# AutoPilotPanel_-_Part_1.net
KiCad netlist of a schematic drawn in EAGLE
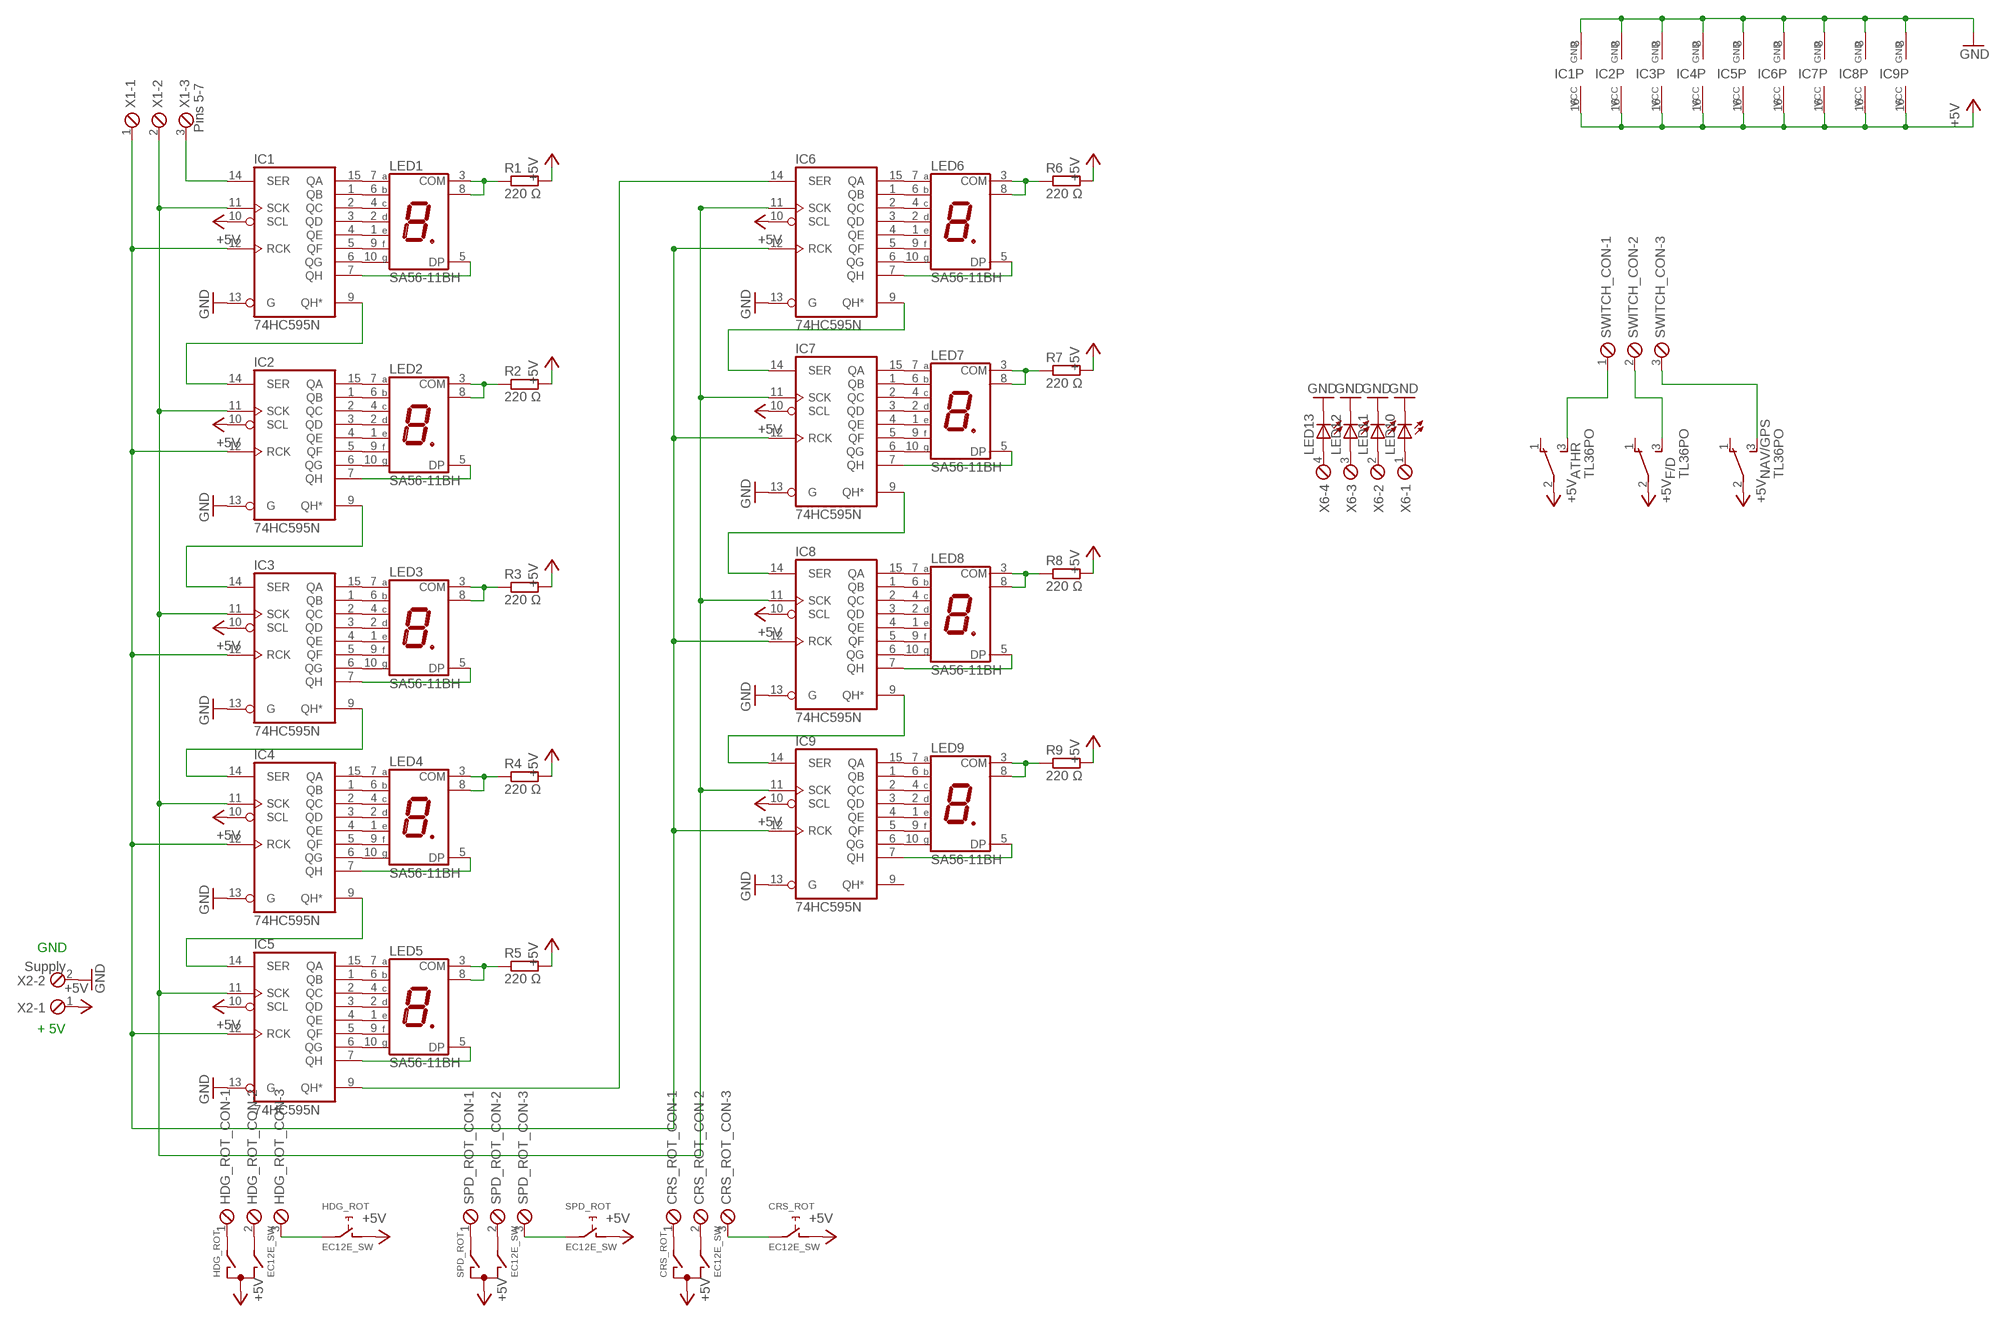
[diagram p0: schematic, sheet 1]

(export (version "E")
  (design (tool "Eeschema 10.0.6"))
  (components
    (comp (ref "ATHR")
      (value "TL36PO")
      (footprint "eagle-import:TL3XPO")
      (libsource (lib "eagle-import") (part "TL36PO"))
    )
    (comp (ref "CRS_ROT")
      (value "EC12E_SW")
      (footprint "eagle-import:ALPS_EC12E_SW")
      (fields (field (name "MPN") "EC12E2424407"))
      (libsource (lib "eagle-import") (part "EC12E_SW"))
    )
    (comp (ref "CRS_ROT_CON")
      (value "MPT3")
      (footprint "eagle-import:3POL254")
      (libsource (lib "eagle-import") (part "MPT3"))
    )
    (comp (ref "F/D")
      (value "TL36PO")
      (footprint "eagle-import:TL3XPO")
      (libsource (lib "eagle-import") (part "TL36PO"))
    )
    (comp (ref "HDG_ROT")
      (value "EC12E_SW")
      (footprint "eagle-import:ALPS_EC12E_SW")
      (fields (field (name "MPN") "EC12E2424407"))
      (libsource (lib "eagle-import") (part "EC12E_SW"))
    )
    (comp (ref "HDG_ROT_CON")
      (value "MPT3")
      (footprint "eagle-import:3POL254")
      (libsource (lib "eagle-import") (part "MPT3"))
    )
    (comp (ref "IC1")
      (value "74HC595N")
      (footprint "eagle-import:DIL16")
      (libsource (lib "eagle-import") (part "74595NHC"))
    )
    (comp (ref "IC2")
      (value "74HC595N")
      (footprint "eagle-import:DIL16")
      (libsource (lib "eagle-import") (part "74595NHC"))
    )
    (comp (ref "IC3")
      (value "74HC595N")
      (footprint "eagle-import:DIL16")
      (libsource (lib "eagle-import") (part "74595NHC"))
    )
    (comp (ref "IC4")
      (value "74HC595N")
      (footprint "eagle-import:DIL16")
      (libsource (lib "eagle-import") (part "74595NHC"))
    )
    (comp (ref "IC5")
      (value "74HC595N")
      (footprint "eagle-import:DIL16")
      (libsource (lib "eagle-import") (part "74595NHC"))
    )
    (comp (ref "IC6")
      (value "74HC595N")
      (footprint "eagle-import:DIL16")
      (libsource (lib "eagle-import") (part "74595NHC"))
    )
    (comp (ref "IC7")
      (value "74HC595N")
      (footprint "eagle-import:DIL16")
      (libsource (lib "eagle-import") (part "74595NHC"))
    )
    (comp (ref "IC8")
      (value "74HC595N")
      (footprint "eagle-import:DIL16")
      (libsource (lib "eagle-import") (part "74595NHC"))
    )
    (comp (ref "IC9")
      (value "74HC595N")
      (footprint "eagle-import:DIL16")
      (libsource (lib "eagle-import") (part "74595NHC"))
    )
    (comp (ref "LED1")
      (value "SA56-11BH")
      (footprint "eagle-import:SA56-11")
      (libsource (lib "eagle-import") (part "7-SEG_SA56-11"))
    )
    (comp (ref "LED2")
      (value "SA56-11BH")
      (footprint "eagle-import:SA56-11")
      (libsource (lib "eagle-import") (part "7-SEG_SA56-11"))
    )
    (comp (ref "LED3")
      (value "SA56-11BH")
      (footprint "eagle-import:SA56-11")
      (libsource (lib "eagle-import") (part "7-SEG_SA56-11"))
    )
    (comp (ref "LED4")
      (value "SA56-11BH")
      (footprint "eagle-import:SA56-11")
      (libsource (lib "eagle-import") (part "7-SEG_SA56-11"))
    )
    (comp (ref "LED5")
      (value "SA56-11BH")
      (footprint "eagle-import:SA56-11")
      (libsource (lib "eagle-import") (part "7-SEG_SA56-11"))
    )
    (comp (ref "LED6")
      (value "SA56-11BH")
      (footprint "eagle-import:SA56-11")
      (libsource (lib "eagle-import") (part "7-SEG_SA56-11"))
    )
    (comp (ref "LED7")
      (value "SA56-11BH")
      (footprint "eagle-import:SA56-11")
      (libsource (lib "eagle-import") (part "7-SEG_SA56-11"))
    )
    (comp (ref "LED8")
      (value "SA56-11BH")
      (footprint "eagle-import:SA56-11")
      (libsource (lib "eagle-import") (part "7-SEG_SA56-11"))
    )
    (comp (ref "LED9")
      (value "SA56-11BH")
      (footprint "eagle-import:SA56-11")
      (libsource (lib "eagle-import") (part "7-SEG_SA56-11"))
    )
    (comp (ref "LED10")
      (value "LED5MM")
      (footprint "eagle-import:LED5MM")
      (libsource (lib "eagle-import") (part "LED5MM"))
    )
    (comp (ref "LED11")
      (value "LED5MM")
      (footprint "eagle-import:LED5MM")
      (libsource (lib "eagle-import") (part "LED5MM"))
    )
    (comp (ref "LED12")
      (value "LED5MM")
      (footprint "eagle-import:LED5MM")
      (libsource (lib "eagle-import") (part "LED5MM"))
    )
    (comp (ref "LED13")
      (value "LED5MM")
      (footprint "eagle-import:LED5MM")
      (libsource (lib "eagle-import") (part "LED5MM"))
    )
    (comp (ref "NAV/GPS")
      (value "TL36PO")
      (footprint "eagle-import:TL3XPO")
      (libsource (lib "eagle-import") (part "TL36PO"))
    )
    (comp (ref "R1")
      (value "220 Ω")
      (footprint "eagle-import:0207_12")
      (libsource (lib "eagle-import") (part "R-EU_0207/12"))
    )
    (comp (ref "R2")
      (value "220 Ω")
      (footprint "eagle-import:0207_12")
      (libsource (lib "eagle-import") (part "R-EU_0207/12"))
    )
    (comp (ref "R3")
      (value "220 Ω")
      (footprint "eagle-import:0207_12")
      (libsource (lib "eagle-import") (part "R-EU_0207/12"))
    )
    (comp (ref "R4")
      (value "220 Ω")
      (footprint "eagle-import:0207_12")
      (libsource (lib "eagle-import") (part "R-EU_0207/12"))
    )
    (comp (ref "R5")
      (value "220 Ω")
      (footprint "eagle-import:0207_12")
      (libsource (lib "eagle-import") (part "R-EU_0207/12"))
    )
    (comp (ref "R6")
      (value "220 Ω")
      (footprint "eagle-import:0207_12")
      (libsource (lib "eagle-import") (part "R-EU_0207/12"))
    )
    (comp (ref "R7")
      (value "220 Ω")
      (footprint "eagle-import:0207_12")
      (libsource (lib "eagle-import") (part "R-EU_0207/12"))
    )
    (comp (ref "R8")
      (value "220 Ω")
      (footprint "eagle-import:0207_12")
      (libsource (lib "eagle-import") (part "R-EU_0207/12"))
    )
    (comp (ref "R9")
      (value "220 Ω")
      (footprint "eagle-import:0207_12")
      (libsource (lib "eagle-import") (part "R-EU_0207/12"))
    )
    (comp (ref "SPD_ROT")
      (value "EC12E_SW")
      (footprint "eagle-import:ALPS_EC12E_SW")
      (fields (field (name "MPN") "EC12E2424407"))
      (libsource (lib "eagle-import") (part "EC12E_SW"))
    )
    (comp (ref "SPD_ROT_CON")
      (value "MPT3")
      (footprint "eagle-import:3POL254")
      (libsource (lib "eagle-import") (part "MPT3"))
    )
    (comp (ref "SWITCH_CON")
      (value "MPT3")
      (footprint "eagle-import:3POL254")
      (libsource (lib "eagle-import") (part "MPT3"))
    )
    (comp (ref "X1")
      (value "Pins 5-7")
      (footprint "eagle-import:3POL254")
      (libsource (lib "eagle-import") (part "MPT3"))
    )
    (comp (ref "X2")
      (value "Supply")
      (footprint "eagle-import:2POL254")
      (libsource (lib "eagle-import") (part "MPT2"))
    )
    (comp (ref "X6")
      (value "MPT4")
      (footprint "eagle-import:4POL254")
      (libsource (lib "eagle-import") (part "MPT4"))
    )
  )
  (nets
    (net (code "1") (name "+5V") (class "Default")
      (node (ref "ATHR") (pin "2") (pinfunction "P_2") (pintype "passive"))
      (node (ref "CRS_ROT") (pin "C") (pinfunction "C_C") (pintype "passive"))
      (node (ref "CRS_ROT") (pin "D") (pinfunction "1_D") (pintype "passive"))
      (node (ref "F/D") (pin "2") (pinfunction "P_2") (pintype "passive"))
      (node (ref "HDG_ROT") (pin "C") (pinfunction "C_C") (pintype "passive"))
      (node (ref "HDG_ROT") (pin "D") (pinfunction "1_D") (pintype "passive"))
      (node (ref "IC1") (pin "10") (pinfunction "SCL_10") (pintype "input"))
      (node (ref "IC1") (pin "16") (pinfunction "VCC_16") (pintype "power_in"))
      (node (ref "IC2") (pin "10") (pinfunction "SCL_10") (pintype "input"))
      (node (ref "IC2") (pin "16") (pinfunction "VCC_16") (pintype "power_in"))
      (node (ref "IC3") (pin "10") (pinfunction "SCL_10") (pintype "input"))
      (node (ref "IC3") (pin "16") (pinfunction "VCC_16") (pintype "power_in"))
      (node (ref "IC4") (pin "10") (pinfunction "SCL_10") (pintype "input"))
      (node (ref "IC4") (pin "16") (pinfunction "VCC_16") (pintype "power_in"))
      (node (ref "IC5") (pin "10") (pinfunction "SCL_10") (pintype "input"))
      (node (ref "IC5") (pin "16") (pinfunction "VCC_16") (pintype "power_in"))
      (node (ref "IC6") (pin "10") (pinfunction "SCL_10") (pintype "input"))
      (node (ref "IC6") (pin "16") (pinfunction "VCC_16") (pintype "power_in"))
      (node (ref "IC7") (pin "10") (pinfunction "SCL_10") (pintype "input"))
      (node (ref "IC7") (pin "16") (pinfunction "VCC_16") (pintype "power_in"))
      (node (ref "IC8") (pin "10") (pinfunction "SCL_10") (pintype "input"))
      (node (ref "IC8") (pin "16") (pinfunction "VCC_16") (pintype "power_in"))
      (node (ref "IC9") (pin "10") (pinfunction "SCL_10") (pintype "input"))
      (node (ref "IC9") (pin "16") (pinfunction "VCC_16") (pintype "power_in"))
      (node (ref "NAV/GPS") (pin "2") (pinfunction "P_2") (pintype "passive"))
      (node (ref "R1") (pin "2") (pinfunction "2_2") (pintype "passive"))
      (node (ref "R2") (pin "2") (pinfunction "2_2") (pintype "passive"))
      (node (ref "R3") (pin "2") (pinfunction "2_2") (pintype "passive"))
      (node (ref "R4") (pin "2") (pinfunction "2_2") (pintype "passive"))
      (node (ref "R5") (pin "2") (pinfunction "2_2") (pintype "passive"))
      (node (ref "R6") (pin "2") (pinfunction "2_2") (pintype "passive"))
      (node (ref "R7") (pin "2") (pinfunction "2_2") (pintype "passive"))
      (node (ref "R8") (pin "2") (pinfunction "2_2") (pintype "passive"))
      (node (ref "R9") (pin "2") (pinfunction "2_2") (pintype "passive"))
      (node (ref "SPD_ROT") (pin "C") (pinfunction "C_C") (pintype "passive"))
      (node (ref "SPD_ROT") (pin "D") (pinfunction "1_D") (pintype "passive"))
      (node (ref "X2") (pin "1") (pinfunction "1_1") (pintype "passive"))
    )
    (net (code "2") (name "GND") (class "Default")
      (node (ref "IC1") (pin "13") (pinfunction "G_13") (pintype "input"))
      (node (ref "IC1") (pin "8") (pinfunction "GND_8") (pintype "power_in"))
      (node (ref "IC2") (pin "13") (pinfunction "G_13") (pintype "input"))
      (node (ref "IC2") (pin "8") (pinfunction "GND_8") (pintype "power_in"))
      (node (ref "IC3") (pin "13") (pinfunction "G_13") (pintype "input"))
      (node (ref "IC3") (pin "8") (pinfunction "GND_8") (pintype "power_in"))
      (node (ref "IC4") (pin "13") (pinfunction "G_13") (pintype "input"))
      (node (ref "IC4") (pin "8") (pinfunction "GND_8") (pintype "power_in"))
      (node (ref "IC5") (pin "13") (pinfunction "G_13") (pintype "input"))
      (node (ref "IC5") (pin "8") (pinfunction "GND_8") (pintype "power_in"))
      (node (ref "IC6") (pin "13") (pinfunction "G_13") (pintype "input"))
      (node (ref "IC6") (pin "8") (pinfunction "GND_8") (pintype "power_in"))
      (node (ref "IC7") (pin "13") (pinfunction "G_13") (pintype "input"))
      (node (ref "IC7") (pin "8") (pinfunction "GND_8") (pintype "power_in"))
      (node (ref "IC8") (pin "13") (pinfunction "G_13") (pintype "input"))
      (node (ref "IC8") (pin "8") (pinfunction "GND_8") (pintype "power_in"))
      (node (ref "IC9") (pin "13") (pinfunction "G_13") (pintype "input"))
      (node (ref "IC9") (pin "8") (pinfunction "GND_8") (pintype "power_in"))
      (node (ref "LED10") (pin "K") (pinfunction "C_K") (pintype "passive"))
      (node (ref "LED11") (pin "K") (pinfunction "C_K") (pintype "passive"))
      (node (ref "LED12") (pin "K") (pinfunction "C_K") (pintype "passive"))
      (node (ref "LED13") (pin "K") (pinfunction "C_K") (pintype "passive"))
      (node (ref "X2") (pin "2") (pinfunction "1_2") (pintype "passive"))
    )
    (net (code "3") (name "Net-(ATHR-S)") (class "Default")
      (node (ref "ATHR") (pin "3") (pinfunction "S_3") (pintype "passive"))
      (node (ref "SWITCH_CON") (pin "1") (pinfunction "1_1") (pintype "passive"))
    )
    (net (code "4") (name "Net-(CRS_ROT-PadA)") (class "Default")
      (node (ref "CRS_ROT") (pin "A") (pinfunction "A_A") (pintype "passive"))
      (node (ref "CRS_ROT_CON") (pin "1") (pinfunction "1_1") (pintype "passive"))
    )
    (net (code "5") (name "Net-(CRS_ROTB-2)") (class "Default")
      (node (ref "CRS_ROT") (pin "E") (pinfunction "2_E") (pintype "passive"))
      (node (ref "CRS_ROT_CON") (pin "3") (pinfunction "1_3") (pintype "passive"))
    )
    (net (code "6") (name "Net-(CRS_ROT_CONB-1)") (class "Default")
      (node (ref "CRS_ROT") (pin "B") (pinfunction "B_B") (pintype "passive"))
      (node (ref "CRS_ROT_CON") (pin "2") (pinfunction "1_2") (pintype "passive"))
    )
    (net (code "7") (name "Net-(F/D-S)") (class "Default")
      (node (ref "F/D") (pin "3") (pinfunction "S_3") (pintype "passive"))
      (node (ref "SWITCH_CON") (pin "2") (pinfunction "1_2") (pintype "passive"))
    )
    (net (code "8") (name "Net-(HDG_ROT-PadA)") (class "Default")
      (node (ref "HDG_ROT") (pin "A") (pinfunction "A_A") (pintype "passive"))
      (node (ref "HDG_ROT_CON") (pin "1") (pinfunction "1_1") (pintype "passive"))
    )
    (net (code "9") (name "Net-(HDG_ROTB-2)") (class "Default")
      (node (ref "HDG_ROT") (pin "E") (pinfunction "2_E") (pintype "passive"))
      (node (ref "HDG_ROT_CON") (pin "3") (pinfunction "1_3") (pintype "passive"))
    )
    (net (code "10") (name "Net-(HDG_ROT_CONB-1)") (class "Default")
      (node (ref "HDG_ROT") (pin "B") (pinfunction "B_B") (pintype "passive"))
      (node (ref "HDG_ROT_CON") (pin "2") (pinfunction "1_2") (pintype "passive"))
    )
    (net (code "11") (name "Net-(IC1A-QA)") (class "Default")
      (node (ref "IC1") (pin "15") (pinfunction "QA_15") (pintype "tri_state"))
      (node (ref "LED1") (pin "7") (pinfunction "A_7") (pintype "passive"))
    )
    (net (code "12") (name "Net-(IC1A-QB)") (class "Default")
      (node (ref "IC1") (pin "1") (pinfunction "QB_1") (pintype "tri_state"))
      (node (ref "LED1") (pin "6") (pinfunction "B_6") (pintype "passive"))
    )
    (net (code "13") (name "Net-(IC1A-QC)") (class "Default")
      (node (ref "IC1") (pin "2") (pinfunction "QC_2") (pintype "tri_state"))
      (node (ref "LED1") (pin "4") (pinfunction "C_4") (pintype "passive"))
    )
    (net (code "14") (name "Net-(IC1A-QD)") (class "Default")
      (node (ref "IC1") (pin "3") (pinfunction "QD_3") (pintype "tri_state"))
      (node (ref "LED1") (pin "2") (pinfunction "D_2") (pintype "passive"))
    )
    (net (code "15") (name "Net-(IC1A-QE)") (class "Default")
      (node (ref "IC1") (pin "4") (pinfunction "QE_4") (pintype "tri_state"))
      (node (ref "LED1") (pin "1") (pinfunction "E_1") (pintype "passive"))
    )
    (net (code "16") (name "Net-(IC1A-QF)") (class "Default")
      (node (ref "IC1") (pin "5") (pinfunction "QF_5") (pintype "tri_state"))
      (node (ref "LED1") (pin "9") (pinfunction "F_9") (pintype "passive"))
    )
    (net (code "17") (name "Net-(IC1A-QG)") (class "Default")
      (node (ref "IC1") (pin "6") (pinfunction "QG_6") (pintype "tri_state"))
      (node (ref "LED1") (pin "10") (pinfunction "G_10") (pintype "passive"))
    )
    (net (code "18") (name "Net-(IC1A-QH)") (class "Default")
      (node (ref "IC1") (pin "7") (pinfunction "QH_7") (pintype "tri_state"))
      (node (ref "LED1") (pin "5") (pinfunction "DP_5") (pintype "passive"))
    )
    (net (code "19") (name "Net-(IC1A-QH*)") (class "Default")
      (node (ref "IC1") (pin "9") (pinfunction "QH*_9") (pintype "tri_state"))
      (node (ref "IC2") (pin "14") (pinfunction "SER_14") (pintype "input"))
    )
    (net (code "20") (name "Net-(IC1A-RCK)") (class "Default")
      (node (ref "IC1") (pin "12") (pinfunction "RCK_12") (pintype "input"))
      (node (ref "IC2") (pin "12") (pinfunction "RCK_12") (pintype "input"))
      (node (ref "IC3") (pin "12") (pinfunction "RCK_12") (pintype "input"))
      (node (ref "IC4") (pin "12") (pinfunction "RCK_12") (pintype "input"))
      (node (ref "IC5") (pin "12") (pinfunction "RCK_12") (pintype "input"))
      (node (ref "IC6") (pin "12") (pinfunction "RCK_12") (pintype "input"))
      (node (ref "IC7") (pin "12") (pinfunction "RCK_12") (pintype "input"))
      (node (ref "IC8") (pin "12") (pinfunction "RCK_12") (pintype "input"))
      (node (ref "IC9") (pin "12") (pinfunction "RCK_12") (pintype "input"))
      (node (ref "X1") (pin "1") (pinfunction "1_1") (pintype "passive"))
    )
    (net (code "21") (name "Net-(IC1A-SCK)") (class "Default")
      (node (ref "IC1") (pin "11") (pinfunction "SCK_11") (pintype "input"))
      (node (ref "IC2") (pin "11") (pinfunction "SCK_11") (pintype "input"))
      (node (ref "IC3") (pin "11") (pinfunction "SCK_11") (pintype "input"))
      (node (ref "IC4") (pin "11") (pinfunction "SCK_11") (pintype "input"))
      (node (ref "IC5") (pin "11") (pinfunction "SCK_11") (pintype "input"))
      (node (ref "IC6") (pin "11") (pinfunction "SCK_11") (pintype "input"))
      (node (ref "IC7") (pin "11") (pinfunction "SCK_11") (pintype "input"))
      (node (ref "IC8") (pin "11") (pinfunction "SCK_11") (pintype "input"))
      (node (ref "IC9") (pin "11") (pinfunction "SCK_11") (pintype "input"))
      (node (ref "X1") (pin "2") (pinfunction "1_2") (pintype "passive"))
    )
    (net (code "22") (name "Net-(IC1A-SER)") (class "Default")
      (node (ref "IC1") (pin "14") (pinfunction "SER_14") (pintype "input"))
      (node (ref "X1") (pin "3") (pinfunction "1_3") (pintype "passive"))
    )
    (net (code "23") (name "Net-(IC2A-QA)") (class "Default")
      (node (ref "IC2") (pin "15") (pinfunction "QA_15") (pintype "tri_state"))
      (node (ref "LED2") (pin "7") (pinfunction "A_7") (pintype "passive"))
    )
    (net (code "24") (name "Net-(IC2A-QB)") (class "Default")
      (node (ref "IC2") (pin "1") (pinfunction "QB_1") (pintype "tri_state"))
      (node (ref "LED2") (pin "6") (pinfunction "B_6") (pintype "passive"))
    )
    (net (code "25") (name "Net-(IC2A-QC)") (class "Default")
      (node (ref "IC2") (pin "2") (pinfunction "QC_2") (pintype "tri_state"))
      (node (ref "LED2") (pin "4") (pinfunction "C_4") (pintype "passive"))
    )
    (net (code "26") (name "Net-(IC2A-QD)") (class "Default")
      (node (ref "IC2") (pin "3") (pinfunction "QD_3") (pintype "tri_state"))
      (node (ref "LED2") (pin "2") (pinfunction "D_2") (pintype "passive"))
    )
    (net (code "27") (name "Net-(IC2A-QE)") (class "Default")
      (node (ref "IC2") (pin "4") (pinfunction "QE_4") (pintype "tri_state"))
      (node (ref "LED2") (pin "1") (pinfunction "E_1") (pintype "passive"))
    )
    (net (code "28") (name "Net-(IC2A-QF)") (class "Default")
      (node (ref "IC2") (pin "5") (pinfunction "QF_5") (pintype "tri_state"))
      (node (ref "LED2") (pin "9") (pinfunction "F_9") (pintype "passive"))
    )
    (net (code "29") (name "Net-(IC2A-QG)") (class "Default")
      (node (ref "IC2") (pin "6") (pinfunction "QG_6") (pintype "tri_state"))
      (node (ref "LED2") (pin "10") (pinfunction "G_10") (pintype "passive"))
    )
    (net (code "30") (name "Net-(IC2A-QH)") (class "Default")
      (node (ref "IC2") (pin "7") (pinfunction "QH_7") (pintype "tri_state"))
      (node (ref "LED2") (pin "5") (pinfunction "DP_5") (pintype "passive"))
    )
    (net (code "31") (name "Net-(IC2A-QH*)") (class "Default")
      (node (ref "IC2") (pin "9") (pinfunction "QH*_9") (pintype "tri_state"))
      (node (ref "IC3") (pin "14") (pinfunction "SER_14") (pintype "input"))
    )
    (net (code "32") (name "Net-(IC3A-QA)") (class "Default")
      (node (ref "IC3") (pin "15") (pinfunction "QA_15") (pintype "tri_state"))
      (node (ref "LED3") (pin "7") (pinfunction "A_7") (pintype "passive"))
    )
    (net (code "33") (name "Net-(IC3A-QB)") (class "Default")
      (node (ref "IC3") (pin "1") (pinfunction "QB_1") (pintype "tri_state"))
      (node (ref "LED3") (pin "6") (pinfunction "B_6") (pintype "passive"))
    )
    (net (code "34") (name "Net-(IC3A-QC)") (class "Default")
      (node (ref "IC3") (pin "2") (pinfunction "QC_2") (pintype "tri_state"))
      (node (ref "LED3") (pin "4") (pinfunction "C_4") (pintype "passive"))
    )
    (net (code "35") (name "Net-(IC3A-QD)") (class "Default")
      (node (ref "IC3") (pin "3") (pinfunction "QD_3") (pintype "tri_state"))
      (node (ref "LED3") (pin "2") (pinfunction "D_2") (pintype "passive"))
    )
    (net (code "36") (name "Net-(IC3A-QE)") (class "Default")
      (node (ref "IC3") (pin "4") (pinfunction "QE_4") (pintype "tri_state"))
      (node (ref "LED3") (pin "1") (pinfunction "E_1") (pintype "passive"))
    )
    (net (code "37") (name "Net-(IC3A-QF)") (class "Default")
      (node (ref "IC3") (pin "5") (pinfunction "QF_5") (pintype "tri_state"))
      (node (ref "LED3") (pin "9") (pinfunction "F_9") (pintype "passive"))
    )
    (net (code "38") (name "Net-(IC3A-QG)") (class "Default")
      (node (ref "IC3") (pin "6") (pinfunction "QG_6") (pintype "tri_state"))
      (node (ref "LED3") (pin "10") (pinfunction "G_10") (pintype "passive"))
    )
    (net (code "39") (name "Net-(IC3A-QH)") (class "Default")
      (node (ref "IC3") (pin "7") (pinfunction "QH_7") (pintype "tri_state"))
      (node (ref "LED3") (pin "5") (pinfunction "DP_5") (pintype "passive"))
    )
    (net (code "40") (name "Net-(IC3A-QH*)") (class "Default")
      (node (ref "IC3") (pin "9") (pinfunction "QH*_9") (pintype "tri_state"))
      (node (ref "IC4") (pin "14") (pinfunction "SER_14") (pintype "input"))
    )
    (net (code "41") (name "Net-(IC4A-QA)") (class "Default")
      (node (ref "IC4") (pin "15") (pinfunction "QA_15") (pintype "tri_state"))
      (node (ref "LED4") (pin "7") (pinfunction "A_7") (pintype "passive"))
    )
    (net (code "42") (name "Net-(IC4A-QB)") (class "Default")
      (node (ref "IC4") (pin "1") (pinfunction "QB_1") (pintype "tri_state"))
      (node (ref "LED4") (pin "6") (pinfunction "B_6") (pintype "passive"))
    )
    (net (code "43") (name "Net-(IC4A-QC)") (class "Default")
      (node (ref "IC4") (pin "2") (pinfunction "QC_2") (pintype "tri_state"))
      (node (ref "LED4") (pin "4") (pinfunction "C_4") (pintype "passive"))
    )
    (net (code "44") (name "Net-(IC4A-QD)") (class "Default")
      (node (ref "IC4") (pin "3") (pinfunction "QD_3") (pintype "tri_state"))
      (node (ref "LED4") (pin "2") (pinfunction "D_2") (pintype "passive"))
    )
    (net (code "45") (name "Net-(IC4A-QE)") (class "Default")
      (node (ref "IC4") (pin "4") (pinfunction "QE_4") (pintype "tri_state"))
      (node (ref "LED4") (pin "1") (pinfunction "E_1") (pintype "passive"))
    )
    (net (code "46") (name "Net-(IC4A-QF)") (class "Default")
      (node (ref "IC4") (pin "5") (pinfunction "QF_5") (pintype "tri_state"))
      (node (ref "LED4") (pin "9") (pinfunction "F_9") (pintype "passive"))
    )
    (net (code "47") (name "Net-(IC4A-QG)") (class "Default")
      (node (ref "IC4") (pin "6") (pinfunction "QG_6") (pintype "tri_state"))
      (node (ref "LED4") (pin "10") (pinfunction "G_10") (pintype "passive"))
    )
    (net (code "48") (name "Net-(IC4A-QH)") (class "Default")
      (node (ref "IC4") (pin "7") (pinfunction "QH_7") (pintype "tri_state"))
      (node (ref "LED4") (pin "5") (pinfunction "DP_5") (pintype "passive"))
    )
    (net (code "49") (name "Net-(IC4A-QH*)") (class "Default")
      (node (ref "IC4") (pin "9") (pinfunction "QH*_9") (pintype "tri_state"))
      (node (ref "IC5") (pin "14") (pinfunction "SER_14") (pintype "input"))
    )
    (net (code "50") (name "Net-(IC5A-QA)") (class "Default")
      (node (ref "IC5") (pin "15") (pinfunction "QA_15") (pintype "tri_state"))
      (node (ref "LED5") (pin "7") (pinfunction "A_7") (pintype "passive"))
    )
    (net (code "51") (name "Net-(IC5A-QB)") (class "Default")
      (node (ref "IC5") (pin "1") (pinfunction "QB_1") (pintype "tri_state"))
      (node (ref "LED5") (pin "6") (pinfunction "B_6") (pintype "passive"))
    )
    (net (code "52") (name "Net-(IC5A-QC)") (class "Default")
      (node (ref "IC5") (pin "2") (pinfunction "QC_2") (pintype "tri_state"))
      (node (ref "LED5") (pin "4") (pinfunction "C_4") (pintype "passive"))
    )
    (net (code "53") (name "Net-(IC5A-QD)") (class "Default")
      (node (ref "IC5") (pin "3") (pinfunction "QD_3") (pintype "tri_state"))
      (node (ref "LED5") (pin "2") (pinfunction "D_2") (pintype "passive"))
    )
    (net (code "54") (name "Net-(IC5A-QE)") (class "Default")
      (node (ref "IC5") (pin "4") (pinfunction "QE_4") (pintype "tri_state"))
      (node (ref "LED5") (pin "1") (pinfunction "E_1") (pintype "passive"))
    )
    (net (code "55") (name "Net-(IC5A-QF)") (class "Default")
      (node (ref "IC5") (pin "5") (pinfunction "QF_5") (pintype "tri_state"))
      (node (ref "LED5") (pin "9") (pinfunction "F_9") (pintype "passive"))
    )
    (net (code "56") (name "Net-(IC5A-QG)") (class "Default")
      (node (ref "IC5") (pin "6") (pinfunction "QG_6") (pintype "tri_state"))
      (node (ref "LED5") (pin "10") (pinfunction "G_10") (pintype "passive"))
    )
    (net (code "57") (name "Net-(IC5A-QH)") (class "Default")
      (node (ref "IC5") (pin "7") (pinfunction "QH_7") (pintype "tri_state"))
      (node (ref "LED5") (pin "5") (pinfunction "DP_5") (pintype "passive"))
    )
    (net (code "58") (name "Net-(IC5A-QH*)") (class "Default")
      (node (ref "IC5") (pin "9") (pinfunction "QH*_9") (pintype "tri_state"))
      (node (ref "IC6") (pin "14") (pinfunction "SER_14") (pintype "input"))
    )
    (net (code "59") (name "Net-(IC6A-QA)") (class "Default")
      (node (ref "IC6") (pin "15") (pinfunction "QA_15") (pintype "tri_state"))
      (node (ref "LED6") (pin "7") (pinfunction "A_7") (pintype "passive"))
    )
    (net (code "60") (name "Net-(IC6A-QB)") (class "Default")
      (node (ref "IC6") (pin "1") (pinfunction "QB_1") (pintype "tri_state"))
      (node (ref "LED6") (pin "6") (pinfunction "B_6") (pintype "passive"))
    )
    (net (code "61") (name "Net-(IC6A-QC)") (class "Default")
      (node (ref "IC6") (pin "2") (pinfunction "QC_2") (pintype "tri_state"))
      (node (ref "LED6") (pin "4") (pinfunction "C_4") (pintype "passive"))
    )
    (net (code "62") (name "Net-(IC6A-QD)") (class "Default")
      (node (ref "IC6") (pin "3") (pinfunction "QD_3") (pintype "tri_state"))
      (node (ref "LED6") (pin "2") (pinfunction "D_2") (pintype "passive"))
    )
    (net (code "63") (name "Net-(IC6A-QE)") (class "Default")
      (node (ref "IC6") (pin "4") (pinfunction "QE_4") (pintype "tri_state"))
      (node (ref "LED6") (pin "1") (pinfunction "E_1") (pintype "passive"))
    )
    (net (code "64") (name "Net-(IC6A-QF)") (class "Default")
      (node (ref "IC6") (pin "5") (pinfunction "QF_5") (pintype "tri_state"))
      (node (ref "LED6") (pin "9") (pinfunction "F_9") (pintype "passive"))
    )
    (net (code "65") (name "Net-(IC6A-QG)") (class "Default")
      (node (ref "IC6") (pin "6") (pinfunction "QG_6") (pintype "tri_state"))
      (node (ref "LED6") (pin "10") (pinfunction "G_10") (pintype "passive"))
    )
    (net (code "66") (name "Net-(IC6A-QH)") (class "Default")
      (node (ref "IC6") (pin "7") (pinfunction "QH_7") (pintype "tri_state"))
      (node (ref "LED6") (pin "5") (pinfunction "DP_5") (pintype "passive"))
    )
    (net (code "67") (name "Net-(IC6A-QH*)") (class "Default")
      (node (ref "IC6") (pin "9") (pinfunction "QH*_9") (pintype "tri_state"))
      (node (ref "IC7") (pin "14") (pinfunction "SER_14") (pintype "input"))
    )
    (net (code "68") (name "Net-(IC7A-QA)") (class "Default")
      (node (ref "IC7") (pin "15") (pinfunction "QA_15") (pintype "tri_state"))
      (node (ref "LED7") (pin "7") (pinfunction "A_7") (pintype "passive"))
    )
    (net (code "69") (name "Net-(IC7A-QB)") (class "Default")
      (node (ref "IC7") (pin "1") (pinfunction "QB_1") (pintype "tri_state"))
      (node (ref "LED7") (pin "6") (pinfunction "B_6") (pintype "passive"))
    )
    (net (code "70") (name "Net-(IC7A-QC)") (class "Default")
      (node (ref "IC7") (pin "2") (pinfunction "QC_2") (pintype "tri_state"))
      (node (ref "LED7") (pin "4") (pinfunction "C_4") (pintype "passive"))
    )
    (net (code "71") (name "Net-(IC7A-QD)") (class "Default")
      (node (ref "IC7") (pin "3") (pinfunction "QD_3") (pintype "tri_state"))
      (node (ref "LED7") (pin "2") (pinfunction "D_2") (pintype "passive"))
    )
    (net (code "72") (name "Net-(IC7A-QE)") (class "Default")
      (node (ref "IC7") (pin "4") (pinfunction "QE_4") (pintype "tri_state"))
      (node (ref "LED7") (pin "1") (pinfunction "E_1") (pintype "passive"))
    )
    (net (code "73") (name "Net-(IC7A-QF)") (class "Default")
      (node (ref "IC7") (pin "5") (pinfunction "QF_5") (pintype "tri_state"))
      (node (ref "LED7") (pin "9") (pinfunction "F_9") (pintype "passive"))
    )
    (net (code "74") (name "Net-(IC7A-QG)") (class "Default")
      (node (ref "IC7") (pin "6") (pinfunction "QG_6") (pintype "tri_state"))
      (node (ref "LED7") (pin "10") (pinfunction "G_10") (pintype "passive"))
    )
    (net (code "75") (name "Net-(IC7A-QH)") (class "Default")
      (node (ref "IC7") (pin "7") (pinfunction "QH_7") (pintype "tri_state"))
      (node (ref "LED7") (pin "5") (pinfunction "DP_5") (pintype "passive"))
    )
    (net (code "76") (name "Net-(IC7A-QH*)") (class "Default")
      (node (ref "IC7") (pin "9") (pinfunction "QH*_9") (pintype "tri_state"))
      (node (ref "IC8") (pin "14") (pinfunction "SER_14") (pintype "input"))
    )
    (net (code "77") (name "Net-(IC8A-QA)") (class "Default")
      (node (ref "IC8") (pin "15") (pinfunction "QA_15") (pintype "tri_state"))
      (node (ref "LED8") (pin "7") (pinfunction "A_7") (pintype "passive"))
    )
    (net (code "78") (name "Net-(IC8A-QB)") (class "Default")
      (node (ref "IC8") (pin "1") (pinfunction "QB_1") (pintype "tri_state"))
      (node (ref "LED8") (pin "6") (pinfunction "B_6") (pintype "passive"))
    )
    (net (code "79") (name "Net-(IC8A-QC)") (class "Default")
      (node (ref "IC8") (pin "2") (pinfunction "QC_2") (pintype "tri_state"))
      (node (ref "LED8") (pin "4") (pinfunction "C_4") (pintype "passive"))
    )
    (net (code "80") (name "Net-(IC8A-QD)") (class "Default")
      (node (ref "IC8") (pin "3") (pinfunction "QD_3") (pintype "tri_state"))
      (node (ref "LED8") (pin "2") (pinfunction "D_2") (pintype "passive"))
    )
    (net (code "81") (name "Net-(IC8A-QE)") (class "Default")
      (node (ref "IC8") (pin "4") (pinfunction "QE_4") (pintype "tri_state"))
      (node (ref "LED8") (pin "1") (pinfunction "E_1") (pintype "passive"))
    )
    (net (code "82") (name "Net-(IC8A-QF)") (class "Default")
      (node (ref "IC8") (pin "5") (pinfunction "QF_5") (pintype "tri_state"))
      (node (ref "LED8") (pin "9") (pinfunction "F_9") (pintype "passive"))
    )
    (net (code "83") (name "Net-(IC8A-QG)") (class "Default")
      (node (ref "IC8") (pin "6") (pinfunction "QG_6") (pintype "tri_state"))
      (node (ref "LED8") (pin "10") (pinfunction "G_10") (pintype "passive"))
    )
    (net (code "84") (name "Net-(IC8A-QH)") (class "Default")
      (node (ref "IC8") (pin "7") (pinfunction "QH_7") (pintype "tri_state"))
      (node (ref "LED8") (pin "5") (pinfunction "DP_5") (pintype "passive"))
    )
    (net (code "85") (name "Net-(IC8A-QH*)") (class "Default")
      (node (ref "IC8") (pin "9") (pinfunction "QH*_9") (pintype "tri_state"))
      (node (ref "IC9") (pin "14") (pinfunction "SER_14") (pintype "input"))
    )
    (net (code "86") (name "Net-(IC9A-QA)") (class "Default")
      (node (ref "IC9") (pin "15") (pinfunction "QA_15") (pintype "tri_state"))
      (node (ref "LED9") (pin "7") (pinfunction "A_7") (pintype "passive"))
    )
    (net (code "87") (name "Net-(IC9A-QB)") (class "Default")
      (node (ref "IC9") (pin "1") (pinfunction "QB_1") (pintype "tri_state"))
      (node (ref "LED9") (pin "6") (pinfunction "B_6") (pintype "passive"))
    )
    (net (code "88") (name "Net-(IC9A-QC)") (class "Default")
      (node (ref "IC9") (pin "2") (pinfunction "QC_2") (pintype "tri_state"))
      (node (ref "LED9") (pin "4") (pinfunction "C_4") (pintype "passive"))
    )
    (net (code "89") (name "Net-(IC9A-QD)") (class "Default")
      (node (ref "IC9") (pin "3") (pinfunction "QD_3") (pintype "tri_state"))
      (node (ref "LED9") (pin "2") (pinfunction "D_2") (pintype "passive"))
    )
    (net (code "90") (name "Net-(IC9A-QE)") (class "Default")
      (node (ref "IC9") (pin "4") (pinfunction "QE_4") (pintype "tri_state"))
      (node (ref "LED9") (pin "1") (pinfunction "E_1") (pintype "passive"))
    )
    (net (code "91") (name "Net-(IC9A-QF)") (class "Default")
      (node (ref "IC9") (pin "5") (pinfunction "QF_5") (pintype "tri_state"))
      (node (ref "LED9") (pin "9") (pinfunction "F_9") (pintype "passive"))
    )
    (net (code "92") (name "Net-(IC9A-QG)") (class "Default")
      (node (ref "IC9") (pin "6") (pinfunction "QG_6") (pintype "tri_state"))
      (node (ref "LED9") (pin "10") (pinfunction "G_10") (pintype "passive"))
    )
    (net (code "93") (name "Net-(IC9A-QH)") (class "Default")
      (node (ref "IC9") (pin "7") (pinfunction "QH_7") (pintype "tri_state"))
      (node (ref "LED9") (pin "5") (pinfunction "DP_5") (pintype "passive"))
    )
    (net (code "94") (name "Net-(LED1-COM-Pad3)") (class "Default")
      (node (ref "LED1") (pin "3") (pinfunction "COM_3") (pintype "passive"))
      (node (ref "LED1") (pin "8") (pinfunction "COM_8") (pintype "passive"))
      (node (ref "R1") (pin "1") (pinfunction "1_1") (pintype "passive"))
    )
    (net (code "95") (name "Net-(LED2-COM-Pad3)") (class "Default")
      (node (ref "LED2") (pin "3") (pinfunction "COM_3") (pintype "passive"))
      (node (ref "LED2") (pin "8") (pinfunction "COM_8") (pintype "passive"))
      (node (ref "R2") (pin "1") (pinfunction "1_1") (pintype "passive"))
    )
    (net (code "96") (name "Net-(LED3-COM-Pad3)") (class "Default")
      (node (ref "LED3") (pin "3") (pinfunction "COM_3") (pintype "passive"))
      (node (ref "LED3") (pin "8") (pinfunction "COM_8") (pintype "passive"))
      (node (ref "R3") (pin "1") (pinfunction "1_1") (pintype "passive"))
    )
    (net (code "97") (name "Net-(LED4-COM-Pad3)") (class "Default")
      (node (ref "LED4") (pin "3") (pinfunction "COM_3") (pintype "passive"))
      (node (ref "LED4") (pin "8") (pinfunction "COM_8") (pintype "passive"))
      (node (ref "R4") (pin "1") (pinfunction "1_1") (pintype "passive"))
    )
    (net (code "98") (name "Net-(LED5-COM-Pad3)") (class "Default")
      (node (ref "LED5") (pin "3") (pinfunction "COM_3") (pintype "passive"))
      (node (ref "LED5") (pin "8") (pinfunction "COM_8") (pintype "passive"))
      (node (ref "R5") (pin "1") (pinfunction "1_1") (pintype "passive"))
    )
    (net (code "99") (name "Net-(LED6-COM-Pad3)") (class "Default")
      (node (ref "LED6") (pin "3") (pinfunction "COM_3") (pintype "passive"))
      (node (ref "LED6") (pin "8") (pinfunction "COM_8") (pintype "passive"))
      (node (ref "R6") (pin "1") (pinfunction "1_1") (pintype "passive"))
    )
    (net (code "100") (name "Net-(LED7-COM-Pad3)") (class "Default")
      (node (ref "LED7") (pin "3") (pinfunction "COM_3") (pintype "passive"))
      (node (ref "LED7") (pin "8") (pinfunction "COM_8") (pintype "passive"))
      (node (ref "R7") (pin "1") (pinfunction "1_1") (pintype "passive"))
    )
    (net (code "101") (name "Net-(LED8-COM-Pad3)") (class "Default")
      (node (ref "LED8") (pin "3") (pinfunction "COM_3") (pintype "passive"))
      (node (ref "LED8") (pin "8") (pinfunction "COM_8") (pintype "passive"))
      (node (ref "R8") (pin "1") (pinfunction "1_1") (pintype "passive"))
    )
    (net (code "102") (name "Net-(LED9-COM-Pad3)") (class "Default")
      (node (ref "LED9") (pin "3") (pinfunction "COM_3") (pintype "passive"))
      (node (ref "LED9") (pin "8") (pinfunction "COM_8") (pintype "passive"))
      (node (ref "R9") (pin "1") (pinfunction "1_1") (pintype "passive"))
    )
    (net (code "103") (name "Net-(LED10-PadA)") (class "Default")
      (node (ref "LED10") (pin "A") (pinfunction "A_A") (pintype "passive"))
      (node (ref "X6") (pin "1") (pinfunction "1_1") (pintype "passive"))
    )
    (net (code "104") (name "Net-(NAV/GPS-S)") (class "Default")
      (node (ref "NAV/GPS") (pin "3") (pinfunction "S_3") (pintype "passive"))
      (node (ref "SWITCH_CON") (pin "3") (pinfunction "1_3") (pintype "passive"))
    )
    (net (code "105") (name "Net-(SPD_ROT-PadA)") (class "Default")
      (node (ref "SPD_ROT") (pin "A") (pinfunction "A_A") (pintype "passive"))
      (node (ref "SPD_ROT_CON") (pin "1") (pinfunction "1_1") (pintype "passive"))
    )
    (net (code "106") (name "Net-(SPD_ROTB-2)") (class "Default")
      (node (ref "SPD_ROT") (pin "E") (pinfunction "2_E") (pintype "passive"))
      (node (ref "SPD_ROT_CON") (pin "3") (pinfunction "1_3") (pintype "passive"))
    )
    (net (code "107") (name "Net-(SPD_ROT_CONB-1)") (class "Default")
      (node (ref "SPD_ROT") (pin "B") (pinfunction "B_B") (pintype "passive"))
      (node (ref "SPD_ROT_CON") (pin "2") (pinfunction "1_2") (pintype "passive"))
    )
    (net (code "108") (name "Net-(X6B-1)") (class "Default")
      (node (ref "LED11") (pin "A") (pinfunction "A_A") (pintype "passive"))
      (node (ref "X6") (pin "2") (pinfunction "1_2") (pintype "passive"))
    )
    (net (code "109") (name "Net-(X6C-1)") (class "Default")
      (node (ref "LED12") (pin "A") (pinfunction "A_A") (pintype "passive"))
      (node (ref "X6") (pin "3") (pinfunction "1_3") (pintype "passive"))
    )
    (net (code "110") (name "Net-(X6D-1)") (class "Default")
      (node (ref "LED13") (pin "A") (pinfunction "A_A") (pintype "passive"))
      (node (ref "X6") (pin "4") (pinfunction "1_4") (pintype "passive"))
    )
    (net (code "111") (name "unconnected-(ATHR-O-Pad1)") (class "Default")
      (node (ref "ATHR") (pin "1") (pinfunction "O_1") (pintype "passive"))
    )
    (net (code "112") (name "unconnected-(F/D-O-Pad1)") (class "Default")
      (node (ref "F/D") (pin "1") (pinfunction "O_1") (pintype "passive"))
    )
    (net (code "113") (name "unconnected-(IC9A-QH*-Pad9)") (class "Default")
      (node (ref "IC9") (pin "9") (pinfunction "QH*_9") (pintype "tri_state"))
    )
    (net (code "114") (name "unconnected-(NAV/GPS-O-Pad1)") (class "Default")
      (node (ref "NAV/GPS") (pin "1") (pinfunction "O_1") (pintype "passive"))
    )
  )
)
